# Schematics.net
KiCad netlist of a schematic drawn in Altium Designer
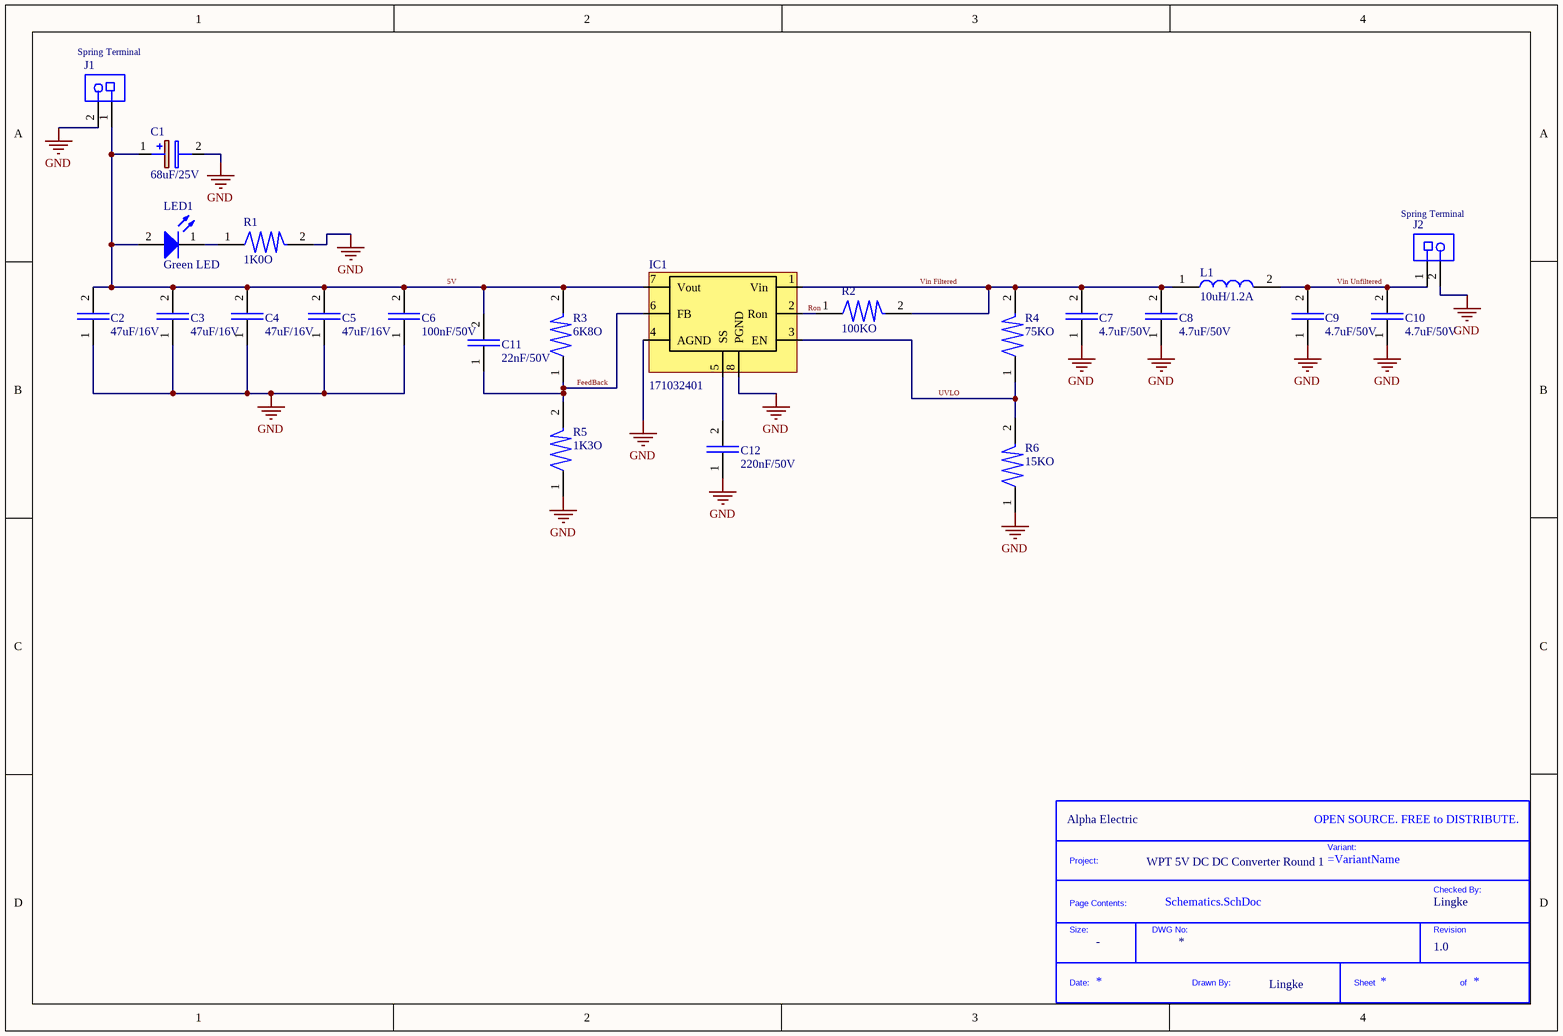
[diagram p0: Schematics.SchDoc]

(export (version "E")
  (design (tool "Eeschema 10.0.6"))
  (components
    (comp (ref "*")
      (value "Title_Block")
      (description "Standard Title Block.")
      (fields
        (field (name "PROJECT NAME") "WPT 5V DC DC Converter Round 1")
        (field (name "COMPANY") "Alpha Electric")
        (field (name "DRAWN BY") "Lingke")
        (field (name "REVISION") "1.0")
        (field (name "DWG NO") "*")
        (field (name "SIZE") "-")
        (field (name "CHECKED BY") "Lingke")
      )
      (libsource (lib "Symbol Library") (part "Title_Block"))
    )
    (comp (ref "C1")
      (value "68uF/25V")
      (footprint "SamacSys:CAPAE830X1170N")
      (description "Capacitor Polarised")
      (fields (field (name "MANUFACTURER_PART_NUMBER") "875075555003"))
      (libsource (lib "Symbol Library") (part "875075555003"))
    )
    (comp (ref "C2")
      (value "47uF/16V")
      (footprint "SamacSys:CAPC3225X280N")
      (description "Capacitor 47uF/16V")
      (libsource (lib "Symbol Library") (part "EMK325ABJ476MMHP"))
    )
    (comp (ref "C3")
      (value "47uF/16V")
      (footprint "SamacSys:CAPC3225X280N")
      (description "Capacitor 47uF/16V")
      (libsource (lib "Symbol Library") (part "EMK325ABJ476MMHP"))
    )
    (comp (ref "C4")
      (value "47uF/16V")
      (footprint "SamacSys:CAPC3225X280N")
      (description "Capacitor 47uF/16V")
      (libsource (lib "Symbol Library") (part "EMK325ABJ476MMHP"))
    )
    (comp (ref "C5")
      (value "47uF/16V")
      (footprint "SamacSys:CAPC3225X280N")
      (description "Capacitor 47uF/16V")
      (libsource (lib "Symbol Library") (part "EMK325ABJ476MMHP"))
    )
    (comp (ref "C6")
      (value "100nF/50V")
      (footprint "SamacSys:CAPC3216X90N")
      (description "Capacitor 100nF/50V")
      (fields
        (field (name "MOUSER2 PART NUMBER") "710-885012208087")
        (field (name "MANUFACTURER_PART_NUMBER") "885012208087")
      )
      (libsource (lib "Symbol Library") (part "885012208087"))
    )
    (comp (ref "C7")
      (value "4.7uF/50V")
      (footprint "SamacSys:CAPC3225X280N")
      (description "Capacitor 4.7uF/50V")
      (fields (field (name "MANUFACTURER_PART_NUMBER") "885012209048"))
      (libsource (lib "Symbol Library") (part "885012209048"))
    )
    (comp (ref "C8")
      (value "4.7uF/50V")
      (footprint "SamacSys:CAPC3225X280N")
      (description "Capacitor 4.7uF/50V")
      (fields (field (name "MANUFACTURER_PART_NUMBER") "885012209048"))
      (libsource (lib "Symbol Library") (part "885012209048"))
    )
    (comp (ref "C9")
      (value "4.7uF/50V")
      (footprint "SamacSys:CAPC3225X280N")
      (description "Capacitor 4.7uF/50V")
      (fields (field (name "MANUFACTURER_PART_NUMBER") "885012209048"))
      (libsource (lib "Symbol Library") (part "885012209048"))
    )
    (comp (ref "C10")
      (value "4.7uF/50V")
      (footprint "SamacSys:CAPC3225X280N")
      (description "Capacitor 4.7uF/50V")
      (fields (field (name "MANUFACTURER_PART_NUMBER") "885012209048"))
      (libsource (lib "Symbol Library") (part "885012209048"))
    )
    (comp (ref "C11")
      (value "22nF/50V")
      (footprint "SamacSys:CAPC2012X90N")
      (description "Capacitor 22nF/50V")
      (fields
        (field (name "MOUSER2 PART NUMBER") "710-885012207094")
        (field (name "MANUFACTURER_PART_NUMBER") "885012207094")
      )
      (libsource (lib "Symbol Library") (part "885012207094"))
    )
    (comp (ref "C12")
      (value "220nF/50V")
      (footprint "SamacSys:CAPC2012X90N")
      (description "Capacitor 220nF / 50V")
      (libsource (lib "Symbol Library") (part "885012207100"))
    )
    (comp (ref "IC1")
      (value "171032401")
      (footprint "7 PIN PFM")
      (description "MagI³C-VDRM Variable Step Down Regulator Module WE-VDRM , Ui=6-42V")
      (fields (field (name "MANUFACTURER") "Wuerth Elektronik"))
      (libsource (lib "Symbol Library") (part "171032401"))
    )
    (comp (ref "J1")
      (value "Spring Terminal")
      (footprint "691411510002")
      (description "Serie 4115 - 5.08mm Screwless Horizontal Entry WR-TBL, 2 pin")
      (fields
        (field (name "PART NUMBER") "691411510002")
        (field (name "MANUFACTURER") "Wurth Elektronik")
        (field (name "PUBLISHER") "WurthElektronik")
      )
      (libsource (lib "Symbol Library") (part "691411510002"))
    )
    (comp (ref "J2")
      (value "Spring Terminal")
      (footprint "691411510002")
      (description "Serie 4115 - 5.08mm Screwless Horizontal Entry WR-TBL, 2 pin")
      (fields
        (field (name "PART NUMBER") "691411510002")
        (field (name "MANUFACTURER") "Wurth Elektronik")
        (field (name "PUBLISHER") "WurthElektronik")
      )
      (libsource (lib "") (part "691411510002_1"))
    )
    (comp (ref "L1")
      (value "10uH/1.2A")
      (footprint "SamacSys:WE-MAPI_3020")
      (description "Inductor")
      (fields (field (name "MANUFACTURER_PART_NUMBER") "74438336100"))
      (libsource (lib "Symbol Library") (part "74438336100"))
    )
    (comp (ref "LED1")
      (value "Green LED")
      (footprint "0805_A")
      (description "SMD mono-color Chip LED, WL-SMCW, Green")
      (fields (field (name "PARTNUMBER") "150080GS75000") (field (name "MANUFACTURER") "Wuerth Elektronik"))
      (libsource (lib "Symbol Library") (part "150080GS75000"))
    )
    (comp (ref "R1")
      (value "1K0O")
      (footprint "FP-CRCW0805-e3-MFG")
      (description "Resistor 1K0 Ohm")
      (libsource (lib "Symbol Library") (part "CRCW08051K00FKEAC"))
    )
    (comp (ref "R2")
      (value "100KO")
      (footprint "FP-CRCW0805-e3-MFG")
      (description "Resistor 100K Ohm")
      (libsource (lib "Symbol Library") (part "CRCW0805100KFKEB"))
    )
    (comp (ref "R3")
      (value "6K8O")
      (footprint "FP-CRCW0805-e3-MFG")
      (description "Resistor 6K8 Ohm")
      (libsource (lib "Symbol Library") (part "CRCW08056K80FKEA"))
    )
    (comp (ref "R4")
      (value "75KO")
      (footprint "FP-CRCW0805-e3-MFG")
      (description "Resistor 75K Ohm")
      (libsource (lib "Symbol Library") (part "CRCW080575K0FKEB"))
    )
    (comp (ref "R5")
      (value "1K3O")
      (footprint "FP-CRCW0805-e3-MFG")
      (description "Resistor 1K3 Ohm")
      (libsource (lib "Symbol Library") (part "CRCW08051K30FKEB"))
    )
    (comp (ref "R6")
      (value "15KO")
      (footprint "FP-CRCW0805-e3-MFG")
      (description "Resistor 15K Ohm")
      (libsource (lib "Symbol Library") (part "CRCW080515K0FKEB"))
    )
  )
  (nets
    (net (code "1") (name "/5V") (class "Default")
      (node (ref "C1") (pin "1") (pinfunction "+_1") (pintype "passive"))
      (node (ref "C11") (pin "2") (pinfunction "2_2") (pintype "passive"))
      (node (ref "C2") (pin "2") (pinfunction "2_2") (pintype "passive"))
      (node (ref "C3") (pin "2") (pinfunction "2_2") (pintype "passive"))
      (node (ref "C4") (pin "2") (pinfunction "2_2") (pintype "passive"))
      (node (ref "C5") (pin "2") (pinfunction "2_2") (pintype "passive"))
      (node (ref "C6") (pin "2") (pinfunction "2_2") (pintype "passive"))
      (node (ref "IC1") (pin "7") (pinfunction "Vout_7") (pintype "passive"))
      (node (ref "J1") (pin "1") (pinfunction "1_1") (pintype "passive"))
      (node (ref "LED1") (pin "2") (pinfunction "A_2") (pintype "passive"))
      (node (ref "R3") (pin "2") (pinfunction "2_2") (pintype "passive"))
    )
    (net (code "2") (name "/FeedBack") (class "Default")
      (node (ref "C11") (pin "1") (pinfunction "1_1") (pintype "passive"))
      (node (ref "IC1") (pin "6") (pinfunction "FB_6") (pintype "passive"))
      (node (ref "R3") (pin "1") (pinfunction "1_1") (pintype "passive"))
      (node (ref "R5") (pin "2") (pinfunction "2_2") (pintype "passive"))
    )
    (net (code "3") (name "/Ron") (class "Default")
      (node (ref "IC1") (pin "2") (pinfunction "Ron_2") (pintype "passive"))
      (node (ref "R2") (pin "1") (pinfunction "1_1") (pintype "passive"))
    )
    (net (code "4") (name "/UVLO") (class "Default")
      (node (ref "IC1") (pin "3") (pinfunction "EN_3") (pintype "passive"))
      (node (ref "R4") (pin "1") (pinfunction "1_1") (pintype "passive"))
      (node (ref "R6") (pin "2") (pinfunction "2_2") (pintype "passive"))
    )
    (net (code "5") (name "/Vin Filtered") (class "Default")
      (node (ref "C7") (pin "2") (pinfunction "2_2") (pintype "passive"))
      (node (ref "C8") (pin "2") (pinfunction "2_2") (pintype "passive"))
      (node (ref "IC1") (pin "1") (pinfunction "Vin_1") (pintype "passive"))
      (node (ref "L1") (pin "1") (pinfunction "1_1") (pintype "passive"))
      (node (ref "R2") (pin "2") (pinfunction "2_2") (pintype "passive"))
      (node (ref "R4") (pin "2") (pinfunction "2_2") (pintype "passive"))
    )
    (net (code "6") (name "/Vin Unfiltered") (class "Default")
      (node (ref "C10") (pin "2") (pinfunction "2_2") (pintype "passive"))
      (node (ref "C9") (pin "2") (pinfunction "2_2") (pintype "passive"))
      (node (ref "J2") (pin "1") (pinfunction "1_1") (pintype "passive"))
      (node (ref "L1") (pin "2") (pinfunction "2_2") (pintype "passive"))
    )
    (net (code "7") (name "GND") (class "Default")
      (node (ref "C1") (pin "2") (pinfunction "-_2") (pintype "passive"))
      (node (ref "C10") (pin "1") (pinfunction "1_1") (pintype "passive"))
      (node (ref "C12") (pin "1") (pinfunction "1_1") (pintype "passive"))
      (node (ref "C2") (pin "1") (pinfunction "1_1") (pintype "passive"))
      (node (ref "C3") (pin "1") (pinfunction "1_1") (pintype "passive"))
      (node (ref "C4") (pin "1") (pinfunction "1_1") (pintype "passive"))
      (node (ref "C5") (pin "1") (pinfunction "1_1") (pintype "passive"))
      (node (ref "C6") (pin "1") (pinfunction "1_1") (pintype "passive"))
      (node (ref "C7") (pin "1") (pinfunction "1_1") (pintype "passive"))
      (node (ref "C8") (pin "1") (pinfunction "1_1") (pintype "passive"))
      (node (ref "C9") (pin "1") (pinfunction "1_1") (pintype "passive"))
      (node (ref "IC1") (pin "4") (pinfunction "AGND_4") (pintype "passive"))
      (node (ref "IC1") (pin "8") (pinfunction "PGND_8") (pintype "passive"))
      (node (ref "J1") (pin "2") (pinfunction "2_2") (pintype "passive"))
      (node (ref "J2") (pin "2") (pinfunction "2_2") (pintype "passive"))
      (node (ref "R1") (pin "2") (pinfunction "2_2") (pintype "passive"))
      (node (ref "R5") (pin "1") (pinfunction "1_1") (pintype "passive"))
      (node (ref "R6") (pin "1") (pinfunction "1_1") (pintype "passive"))
    )
    (net (code "8") (name "Net-(IC1-SS)") (class "Default")
      (node (ref "C12") (pin "2") (pinfunction "2_2") (pintype "passive"))
      (node (ref "IC1") (pin "5") (pinfunction "SS_5") (pintype "passive"))
    )
    (net (code "9") (name "Net-(LED1-K)") (class "Default")
      (node (ref "LED1") (pin "1") (pinfunction "K_1") (pintype "passive"))
      (node (ref "R1") (pin "1") (pinfunction "1_1") (pintype "passive"))
    )
  )
)
